# SlotCarControllerRev1.net
KiCad netlist of a schematic drawn in Altium Designer
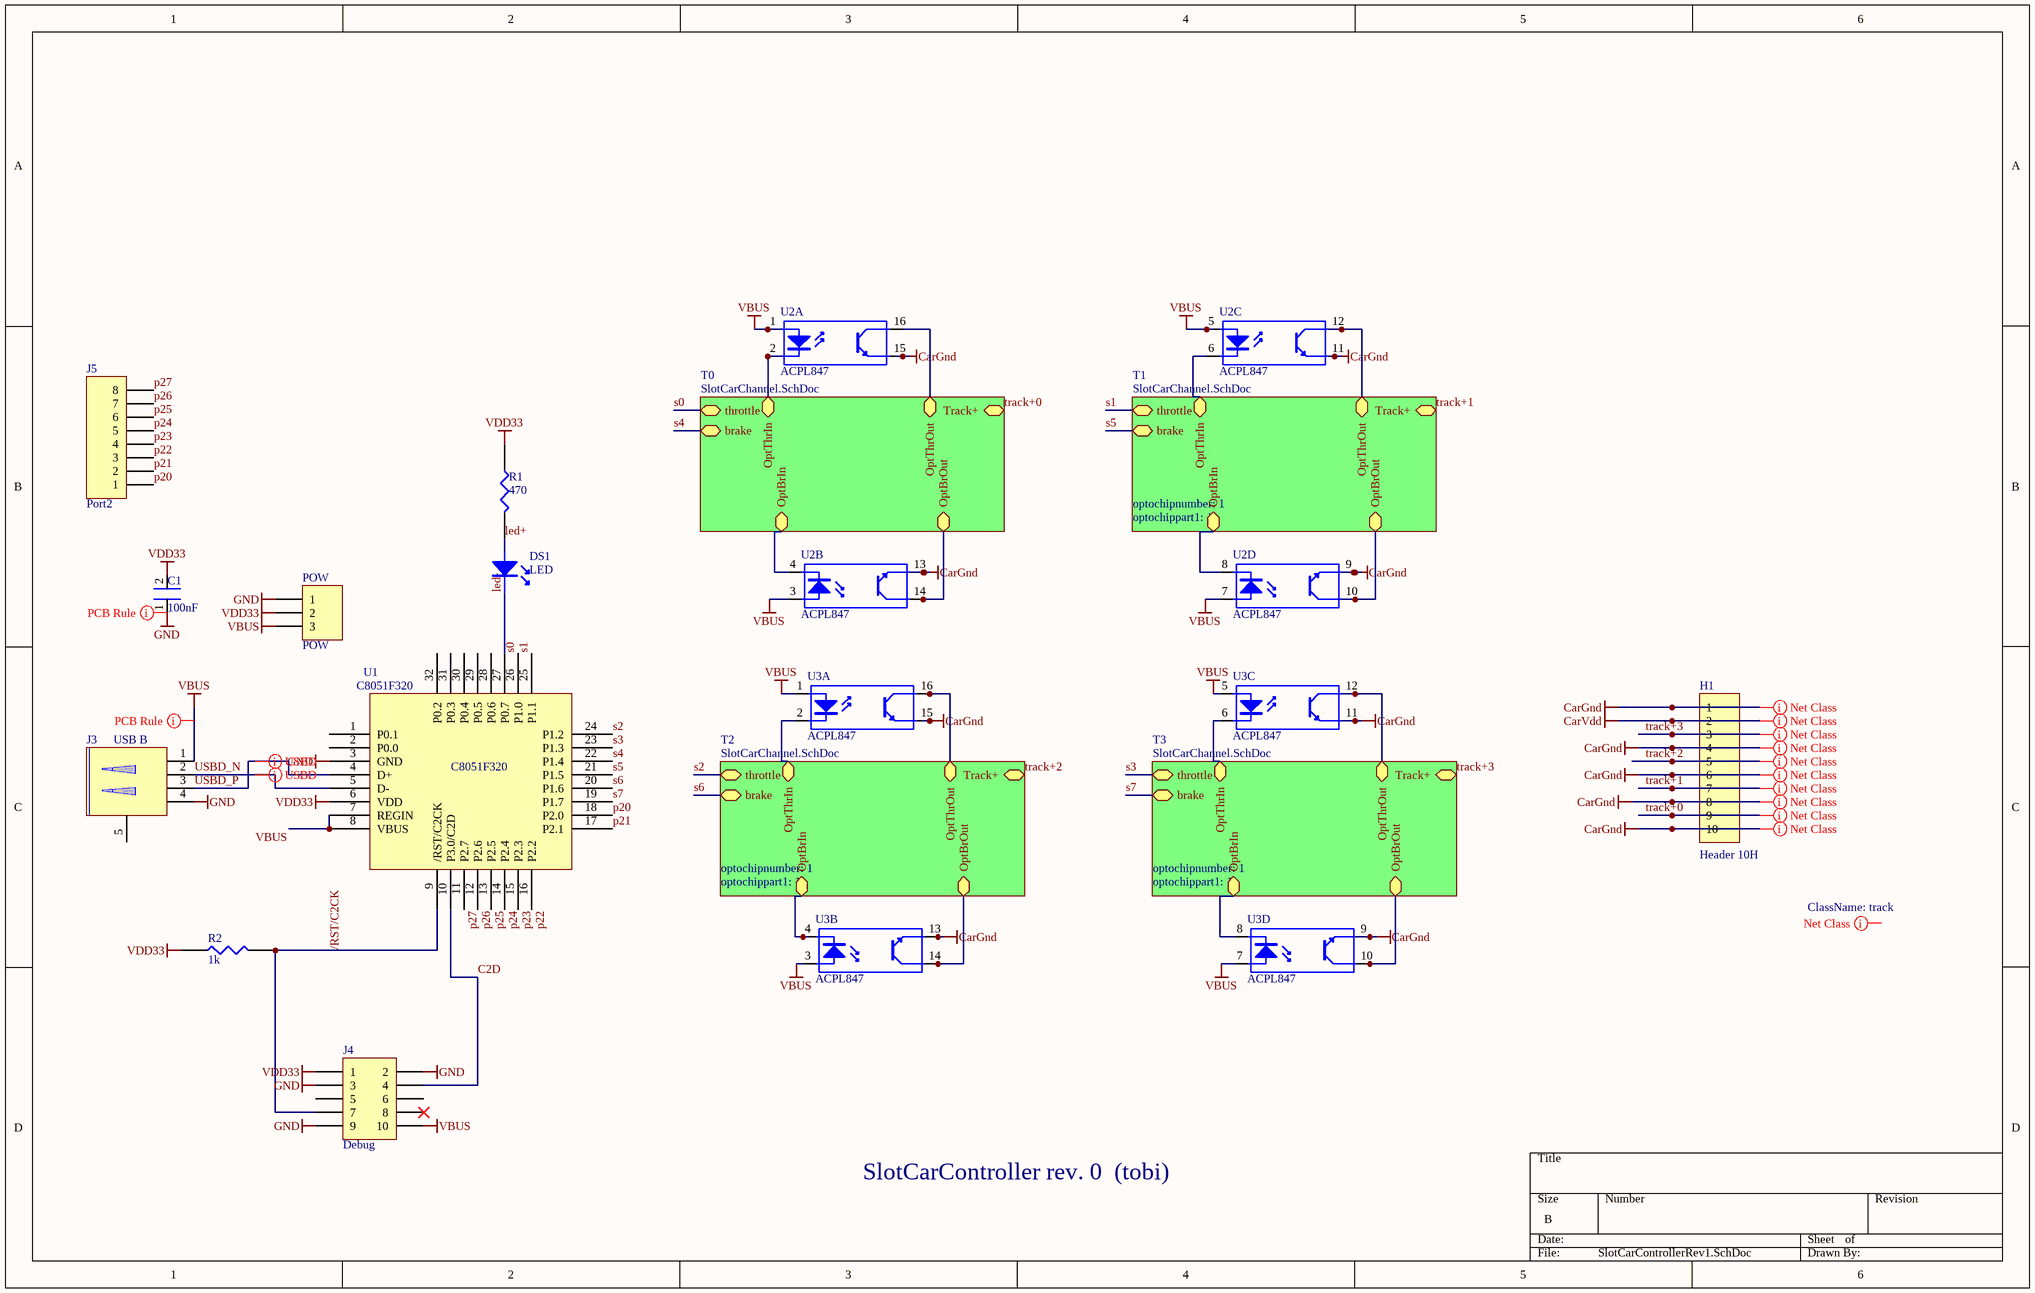
[diagram p0: SlotCarControllerRev1.SchDoc]

(export (version "E")
  (design (tool "Eeschema 10.0.6"))
  (components
    (comp (ref "C1")
      (value "100nF")
      (footprint "CC1608-0603")
      (libsource (lib "tobi SCHEMATIC") (part "CAPCHIP"))
    )
    (comp (ref "DS1")
      (value "LED")
      (footprint "0805LED")
      (description "LED, SMT 3mm by 1.5mm")
      (libsource (lib "SimpleMonitorUSBAER") (part "LED"))
    )
    (comp (ref "H1")
      (value "Header 10H")
      (footprint "SL508/10/90")
      (description "Header, 10-Pin, Right Angle")
      (fields (field (name "PUBLISHER") "Altium Limited"))
      (libsource (lib "Miscellaneous Connectors") (part "Header 10H"))
    )
    (comp (ref "J3")
      (value "USB B")
      (footprint "usb")
      (description "USB TypB")
      (libsource (lib "DAC") (part "USB"))
    )
    (comp (ref "J4")
      (value "Debug")
      (footprint "HDR2X5")
      (description "Header, 5-Pin, Dual row")
      (fields (field (name "PUBLISHER") "Altium Limited"))
      (libsource (lib "Miscellaneous Connectors") (part "Header 5X2"))
    )
    (comp (ref "J5")
      (value "Port2")
      (footprint "HDR1X8")
      (description "Header, 8-Pin")
      (fields (field (name "PUBLISHER") "Altium Limited"))
      (libsource (lib "Miscellaneous Connectors") (part "Header 8"))
    )
    (comp (ref "POW")
      (value "POW")
      (footprint "HDR1X3")
      (description "Header, 3-Pin")
      (fields (field (name "PUBLISHER") "Altium Limited"))
      (libsource (lib "Miscellaneous Connectors") (part "Header 3"))
    )
    (comp (ref "R1") (value "470") (footprint "CR1608-0603") (libsource (lib "*") (part "RES1")))
    (comp (ref "R2") (value "1k") (footprint "CR1608-0603") (libsource (lib "*") (part "RES1")))
    (comp (ref "U1")
      (value "C8051F320")
      (footprint "TQFP32")
      (description "Silicon Labs USB Microcontroller")
      (libsource (lib "tobi SCHEMATIC") (part "C8051F320"))
    )
    (comp (ref "U2")
      (value "ACPL847")
      (footprint "DIP16")
      (description "16-Pin 4-channel Phototransistor Optocoupler")
      (fields (field (name "PUBLISHER") "tobi"))
      (libsource (lib "SlotCarController") (part "Opto16"))
    )
    (comp (ref "U3")
      (value "ACPL847")
      (footprint "DIP16")
      (description "16-Pin 4-channel Phototransistor Optocoupler")
      (fields (field (name "PUBLISHER") "tobi"))
      (libsource (lib "SlotCarController") (part "Opto16"))
    )
  )
  (nets
    (net (code "1") (name "/C2D") (class "Default")
      (node (ref "J4") (pin "4") (pinfunction "4_4") (pintype "passive"))
      (node (ref "U1") (pin "10") (pinfunction "P3.0/C2D_10") (pintype "passive"))
    )
    (net (code "2") (name "/OptBrIn") (class "Default")
      (node (ref "U3") (pin "8") (pinfunction "8_8") (pintype "passive"))
    )
    (net (code "3") (name "/OptBrIn_1") (class "Default")
      (node (ref "U2") (pin "8") (pinfunction "8_8") (pintype "passive"))
    )
    (net (code "4") (name "/OptBrIn_2") (class "Default")
      (node (ref "U2") (pin "4") (pinfunction "4_4") (pintype "passive"))
    )
    (net (code "5") (name "/OptBrIn_3") (class "Default")
      (node (ref "U3") (pin "4") (pinfunction "4_4") (pintype "passive"))
    )
    (net (code "6") (name "/OptBrOut") (class "Default")
      (node (ref "U3") (pin "10") (pinfunction "10_10") (pintype "passive"))
    )
    (net (code "7") (name "/OptBrOut_1") (class "Default")
      (node (ref "U2") (pin "10") (pinfunction "10_10") (pintype "passive"))
    )
    (net (code "8") (name "/OptBrOut_2") (class "Default")
      (node (ref "U2") (pin "14") (pinfunction "14_14") (pintype "passive"))
    )
    (net (code "9") (name "/OptBrOut_3") (class "Default")
      (node (ref "U3") (pin "14") (pinfunction "14_14") (pintype "passive"))
    )
    (net (code "10") (name "/OptThrIn") (class "Default")
      (node (ref "U2") (pin "2") (pinfunction "K_2") (pintype "passive"))
    )
    (net (code "11") (name "/OptThrIn_1") (class "Default")
      (node (ref "U2") (pin "6") (pinfunction "6_6") (pintype "passive"))
    )
    (net (code "12") (name "/OptThrIn_2") (class "Default")
      (node (ref "U3") (pin "6") (pinfunction "6_6") (pintype "passive"))
    )
    (net (code "13") (name "/OptThrIn_3") (class "Default")
      (node (ref "U3") (pin "2") (pinfunction "K_2") (pintype "passive"))
    )
    (net (code "14") (name "/OptThrOut") (class "Default")
      (node (ref "U2") (pin "16") (pinfunction "16_16") (pintype "passive"))
    )
    (net (code "15") (name "/OptThrOut_1") (class "Default")
      (node (ref "U3") (pin "12") (pinfunction "12_12") (pintype "passive"))
    )
    (net (code "16") (name "/OptThrOut_2") (class "Default")
      (node (ref "U2") (pin "12") (pinfunction "12_12") (pintype "passive"))
    )
    (net (code "17") (name "/OptThrOut_3") (class "Default")
      (node (ref "U3") (pin "16") (pinfunction "16_16") (pintype "passive"))
    )
    (net (code "18") (name "/USBD_N") (class "Default")
      (node (ref "J3") (pin "2") (pintype "passive"))
      (node (ref "U1") (pin "5") (pinfunction "D-_5") (pintype "passive"))
    )
    (net (code "19") (name "/USBD_P") (class "Default")
      (node (ref "J3") (pin "3") (pintype "passive"))
      (node (ref "U1") (pin "4") (pinfunction "D+_4") (pintype "passive"))
    )
    (net (code "20") (name "/led+") (class "Default")
      (node (ref "DS1") (pin "+") (pinfunction "1_+") (pintype "passive"))
      (node (ref "R1") (pin "2") (pinfunction "2_2") (pintype "passive"))
    )
    (net (code "21") (name "/led-") (class "Default")
      (node (ref "DS1") (pin "-") (pinfunction "2_-") (pintype "passive"))
      (node (ref "U1") (pin "27") (pinfunction "P0.7_27") (pintype "passive"))
    )
    (net (code "22") (name "/p20") (class "Default")
      (node (ref "J5") (pin "1") (pinfunction "1_1") (pintype "passive"))
      (node (ref "U1") (pin "18") (pinfunction "P2.0_18") (pintype "passive"))
    )
    (net (code "23") (name "/p21") (class "Default")
      (node (ref "J5") (pin "2") (pinfunction "2_2") (pintype "passive"))
      (node (ref "U1") (pin "17") (pinfunction "P2.1_17") (pintype "passive"))
    )
    (net (code "24") (name "/p22") (class "Default")
      (node (ref "J5") (pin "3") (pinfunction "3_3") (pintype "passive"))
      (node (ref "U1") (pin "16") (pinfunction "P2.2_16") (pintype "passive"))
    )
    (net (code "25") (name "/p23") (class "Default")
      (node (ref "J5") (pin "4") (pinfunction "4_4") (pintype "passive"))
      (node (ref "U1") (pin "15") (pinfunction "P2.3_15") (pintype "passive"))
    )
    (net (code "26") (name "/p24") (class "Default")
      (node (ref "J5") (pin "5") (pinfunction "5_5") (pintype "passive"))
      (node (ref "U1") (pin "14") (pinfunction "P2.4_14") (pintype "passive"))
    )
    (net (code "27") (name "/p25") (class "Default")
      (node (ref "J5") (pin "6") (pinfunction "6_6") (pintype "passive"))
      (node (ref "U1") (pin "13") (pinfunction "P2.5_13") (pintype "passive"))
    )
    (net (code "28") (name "/p26") (class "Default")
      (node (ref "J5") (pin "7") (pinfunction "7_7") (pintype "passive"))
      (node (ref "U1") (pin "12") (pinfunction "P2.6_12") (pintype "passive"))
    )
    (net (code "29") (name "/p27") (class "Default")
      (node (ref "J5") (pin "8") (pinfunction "8_8") (pintype "passive"))
      (node (ref "U1") (pin "11") (pinfunction "P2.7_11") (pintype "passive"))
    )
    (net (code "30") (name "/s0") (class "Default")
      (node (ref "U1") (pin "26") (pinfunction "P1.0_26") (pintype "passive"))
    )
    (net (code "31") (name "/s1") (class "Default")
      (node (ref "U1") (pin "25") (pinfunction "P1.1_25") (pintype "passive"))
    )
    (net (code "32") (name "/s2") (class "Default")
      (node (ref "U1") (pin "24") (pinfunction "P1.2_24") (pintype "passive"))
    )
    (net (code "33") (name "/s3") (class "Default")
      (node (ref "U1") (pin "23") (pinfunction "P1.3_23") (pintype "passive"))
    )
    (net (code "34") (name "/s4") (class "Default")
      (node (ref "U1") (pin "22") (pinfunction "P1.4_22") (pintype "passive"))
    )
    (net (code "35") (name "/s5") (class "Default")
      (node (ref "U1") (pin "21") (pinfunction "P1.5_21") (pintype "passive"))
    )
    (net (code "36") (name "/s6") (class "Default")
      (node (ref "U1") (pin "20") (pinfunction "P1.6_20") (pintype "passive"))
    )
    (net (code "37") (name "/s7") (class "Default")
      (node (ref "U1") (pin "19") (pinfunction "P1.7_19") (pintype "passive"))
    )
    (net (code "38") (name "/track+0") (class "Default")
      (node (ref "H1") (pin "9") (pinfunction "9_9") (pintype "passive"))
    )
    (net (code "39") (name "/track+1") (class "Default")
      (node (ref "H1") (pin "7") (pinfunction "7_7") (pintype "passive"))
    )
    (net (code "40") (name "/track+2") (class "Default")
      (node (ref "H1") (pin "5") (pinfunction "5_5") (pintype "passive"))
    )
    (net (code "41") (name "/track+3") (class "Default")
      (node (ref "H1") (pin "3") (pinfunction "3_3") (pintype "passive"))
    )
    (net (code "42") (name "/{slash}RST{slash}C2CK") (class "Default")
      (node (ref "J4") (pin "7") (pinfunction "7_7") (pintype "passive"))
      (node (ref "R2") (pin "2") (pinfunction "2_2") (pintype "passive"))
      (node (ref "U1") (pin "9") (pinfunction "/RST/C2CK_9") (pintype "passive"))
    )
    (net (code "43") (name "CarGnd") (class "Default")
      (node (ref "H1") (pin "1") (pinfunction "1_1") (pintype "passive"))
      (node (ref "H1") (pin "10") (pinfunction "10_10") (pintype "passive"))
      (node (ref "H1") (pin "4") (pinfunction "4_4") (pintype "passive"))
      (node (ref "H1") (pin "6") (pinfunction "6_6") (pintype "passive"))
      (node (ref "H1") (pin "8") (pinfunction "8_8") (pintype "passive"))
      (node (ref "U2") (pin "11") (pinfunction "11_11") (pintype "passive"))
      (node (ref "U2") (pin "13") (pinfunction "13_13") (pintype "passive"))
      (node (ref "U2") (pin "15") (pinfunction "15_15") (pintype "passive"))
      (node (ref "U2") (pin "9") (pinfunction "9_9") (pintype "passive"))
      (node (ref "U3") (pin "11") (pinfunction "11_11") (pintype "passive"))
      (node (ref "U3") (pin "13") (pinfunction "13_13") (pintype "passive"))
      (node (ref "U3") (pin "15") (pinfunction "15_15") (pintype "passive"))
      (node (ref "U3") (pin "9") (pinfunction "9_9") (pintype "passive"))
    )
    (net (code "44") (name "CarVdd") (class "Default")
      (node (ref "H1") (pin "2") (pinfunction "2_2") (pintype "passive"))
    )
    (net (code "45") (name "GND") (class "Default")
      (node (ref "C1") (pin "1") (pintype "passive"))
      (node (ref "J3") (pin "4") (pintype "passive"))
      (node (ref "J4") (pin "2") (pinfunction "2_2") (pintype "passive"))
      (node (ref "J4") (pin "3") (pinfunction "3_3") (pintype "passive"))
      (node (ref "J4") (pin "9") (pinfunction "9_9") (pintype "passive"))
      (node (ref "POW") (pin "1") (pinfunction "1_1") (pintype "passive"))
      (node (ref "U1") (pin "3") (pinfunction "GND_3") (pintype "passive"))
    )
    (net (code "46") (name "VBUS") (class "Default")
      (node (ref "J3") (pin "1") (pintype "passive"))
      (node (ref "J4") (pin "10") (pinfunction "10_10") (pintype "passive"))
      (node (ref "POW") (pin "3") (pinfunction "3_3") (pintype "passive"))
      (node (ref "U1") (pin "7") (pinfunction "REGIN_7") (pintype "passive"))
      (node (ref "U1") (pin "8") (pinfunction "VBUS_8") (pintype "passive"))
      (node (ref "U2") (pin "1") (pinfunction "A_1") (pintype "passive"))
      (node (ref "U2") (pin "3") (pinfunction "3_3") (pintype "passive"))
      (node (ref "U2") (pin "5") (pinfunction "5_5") (pintype "passive"))
      (node (ref "U2") (pin "7") (pinfunction "7_7") (pintype "passive"))
      (node (ref "U3") (pin "1") (pinfunction "A_1") (pintype "passive"))
      (node (ref "U3") (pin "3") (pinfunction "3_3") (pintype "passive"))
      (node (ref "U3") (pin "5") (pinfunction "5_5") (pintype "passive"))
      (node (ref "U3") (pin "7") (pinfunction "7_7") (pintype "passive"))
    )
    (net (code "47") (name "VDD33") (class "Default")
      (node (ref "C1") (pin "2") (pintype "passive"))
      (node (ref "J4") (pin "1") (pinfunction "1_1") (pintype "passive"))
      (node (ref "POW") (pin "2") (pinfunction "2_2") (pintype "passive"))
      (node (ref "R1") (pin "1") (pinfunction "1_1") (pintype "passive"))
      (node (ref "R2") (pin "1") (pinfunction "1_1") (pintype "passive"))
      (node (ref "U1") (pin "6") (pinfunction "VDD_6") (pintype "passive"))
    )
    (net (code "48") (name "unconnected-(J3-Pad5)") (class "Default")
      (node (ref "J3") (pin "5") (pintype "passive"))
    )
    (net (code "49") (name "unconnected-(J4-Pad5)") (class "Default")
      (node (ref "J4") (pin "5") (pinfunction "5_5") (pintype "passive"))
    )
    (net (code "50") (name "unconnected-(J4-Pad6)") (class "Default")
      (node (ref "J4") (pin "6") (pinfunction "6_6") (pintype "passive"))
    )
    (net (code "51") (name "unconnected-(J4-Pad8)") (class "Default")
      (node (ref "J4") (pin "8") (pinfunction "8_8") (pintype "passive+no_connect"))
    )
    (net (code "52") (name "unconnected-(U1-P0.0-Pad2)") (class "Default")
      (node (ref "U1") (pin "2") (pinfunction "P0.0_2") (pintype "passive"))
    )
    (net (code "53") (name "unconnected-(U1-P0.1-Pad1)") (class "Default")
      (node (ref "U1") (pin "1") (pinfunction "P0.1_1") (pintype "passive"))
    )
    (net (code "54") (name "unconnected-(U1-P0.2-Pad32)") (class "Default")
      (node (ref "U1") (pin "32") (pinfunction "P0.2_32") (pintype "passive"))
    )
    (net (code "55") (name "unconnected-(U1-P0.3-Pad31)") (class "Default")
      (node (ref "U1") (pin "31") (pinfunction "P0.3_31") (pintype "passive"))
    )
    (net (code "56") (name "unconnected-(U1-P0.4-Pad30)") (class "Default")
      (node (ref "U1") (pin "30") (pinfunction "P0.4_30") (pintype "passive"))
    )
    (net (code "57") (name "unconnected-(U1-P0.5-Pad29)") (class "Default")
      (node (ref "U1") (pin "29") (pinfunction "P0.5_29") (pintype "passive"))
    )
    (net (code "58") (name "unconnected-(U1-P0.6-Pad28)") (class "Default")
      (node (ref "U1") (pin "28") (pinfunction "P0.6_28") (pintype "passive"))
    )
  )
)
